# ECGv2_Board.net
KiCad netlist of a schematic drawn in EAGLE
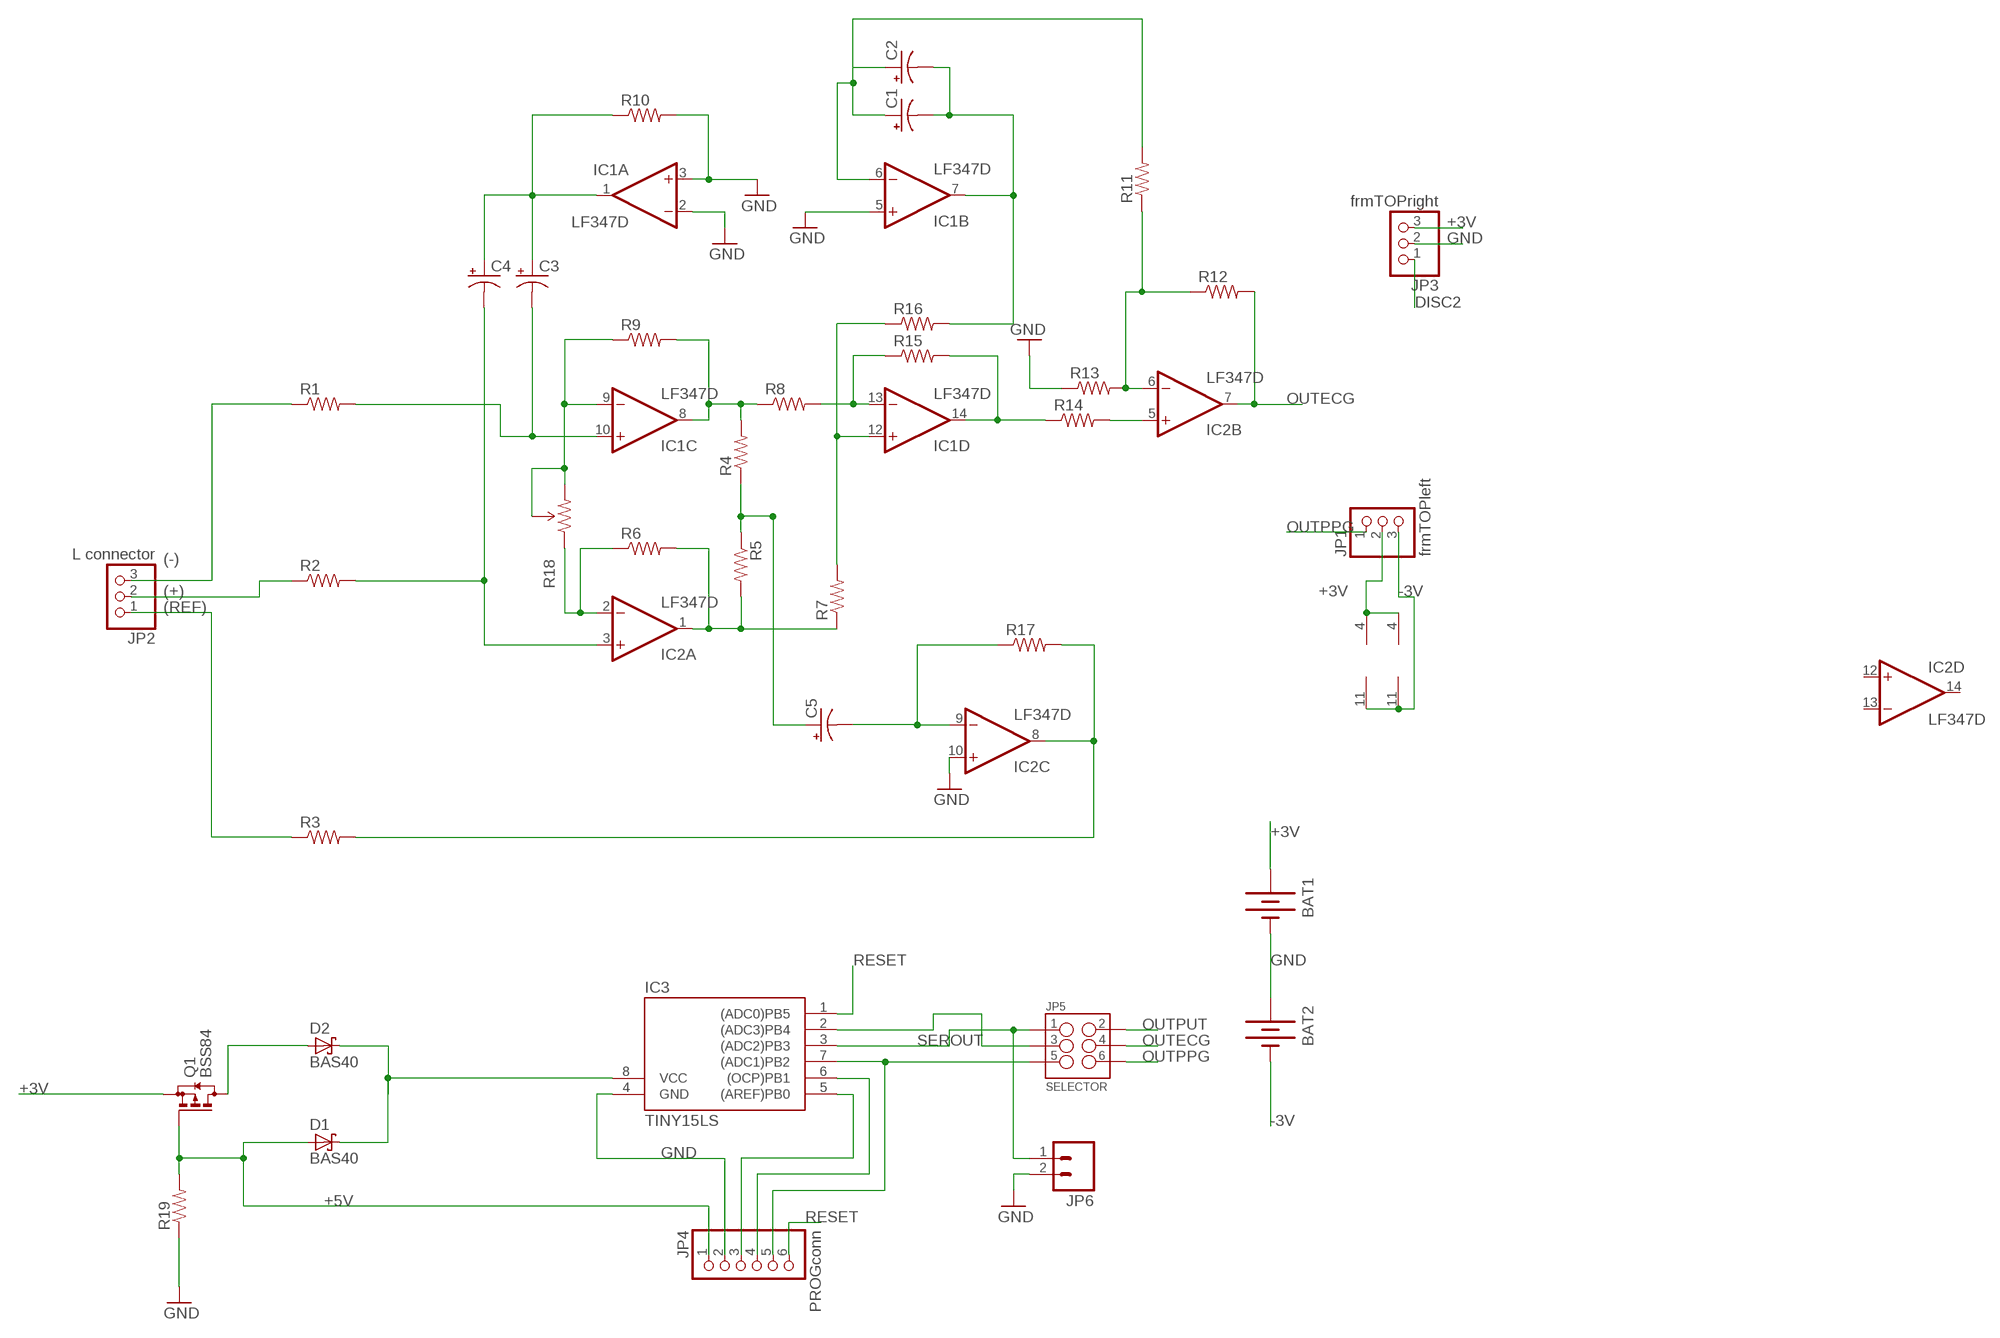
[diagram p0: schematic, sheet 1]

(export (version "E")
  (design (tool "Eeschema 10.0.6"))
  (components
    (comp (ref "BAT1")
      (value "BATTERY245MM")
      (footprint "eagle-import:BATTCON_245MM")
      (libsource (lib "eagle-import") (part "BATTERY245MM"))
    )
    (comp (ref "BAT2")
      (value "BATTERY245MM")
      (footprint "eagle-import:BATTCON_245MM")
      (libsource (lib "eagle-import") (part "BATTERY245MM"))
    )
    (comp (ref "C1")
      (value "CAP_POL1206-KIT")
      (footprint "eagle-import:EIA3216-KIT")
      (libsource (lib "eagle-import") (part "CAP_POL1206-KIT"))
    )
    (comp (ref "C2")
      (value "CAP_POL1206-KIT")
      (footprint "eagle-import:EIA3216-KIT")
      (libsource (lib "eagle-import") (part "CAP_POL1206-KIT"))
    )
    (comp (ref "C3")
      (value "CAP_POL1206-KIT")
      (footprint "eagle-import:EIA3216-KIT")
      (libsource (lib "eagle-import") (part "CAP_POL1206-KIT"))
    )
    (comp (ref "C4")
      (value "CAP_POL1206-KIT")
      (footprint "eagle-import:EIA3216-KIT")
      (libsource (lib "eagle-import") (part "CAP_POL1206-KIT"))
    )
    (comp (ref "C5")
      (value "CAP_POL1206-KIT")
      (footprint "eagle-import:EIA3216-KIT")
      (libsource (lib "eagle-import") (part "CAP_POL1206-KIT"))
    )
    (comp (ref "D1")
      (value "BAS40")
      (footprint "eagle-import:SOT23")
      (libsource (lib "eagle-import") (part "BAS40"))
    )
    (comp (ref "D2")
      (value "BAS40")
      (footprint "eagle-import:SOT23")
      (libsource (lib "eagle-import") (part "BAS40"))
    )
    (comp (ref "IC1")
      (value "LF347D")
      (footprint "eagle-import:SO14")
      (libsource (lib "eagle-import") (part "LF347D"))
    )
    (comp (ref "IC2")
      (value "LF347D")
      (footprint "eagle-import:SO14")
      (libsource (lib "eagle-import") (part "LF347D"))
    )
    (comp (ref "IC3")
      (value "TINY15LS")
      (footprint "eagle-import:SOIC8")
      (libsource (lib "eagle-import") (part "TINY15LS"))
    )
    (comp (ref "JP1")
      (value "frmTOPleft")
      (footprint "eagle-import:1X03")
      (libsource (lib "eagle-import") (part "PINHD-1X3"))
    )
    (comp (ref "JP2")
      (value "L connector")
      (footprint "eagle-import:1X03")
      (libsource (lib "eagle-import") (part "PINHD-1X3"))
    )
    (comp (ref "JP3")
      (value "frmTOPright")
      (footprint "eagle-import:1X03")
      (libsource (lib "eagle-import") (part "PINHD-1X3"))
    )
    (comp (ref "JP4")
      (value "PROGconn")
      (footprint "eagle-import:1X06-BIG")
      (libsource (lib "eagle-import") (part "PINHD-1X6B"))
    )
    (comp (ref "JP5")
      (value "SELECTOR")
      (footprint "eagle-import:2X3")
      (libsource (lib "eagle-import") (part "M03X2FEMALE"))
    )
    (comp (ref "JP6")
      (value "M02PTH")
      (footprint "eagle-import:1X02")
      (libsource (lib "eagle-import") (part "M02PTH"))
    )
    (comp (ref "Q1")
      (value "BSS84")
      (footprint "eagle-import:SOT23")
      (libsource (lib "eagle-import") (part "BSS84"))
    )
    (comp (ref "R1")
      (value "RESISTOR0402-RES")
      (footprint "eagle-import:0402-RES")
      (libsource (lib "eagle-import") (part "RESISTOR0402-RES"))
    )
    (comp (ref "R2")
      (value "RESISTOR0402-RES")
      (footprint "eagle-import:0402-RES")
      (libsource (lib "eagle-import") (part "RESISTOR0402-RES"))
    )
    (comp (ref "R3")
      (value "RESISTOR0402-RES")
      (footprint "eagle-import:0402-RES")
      (libsource (lib "eagle-import") (part "RESISTOR0402-RES"))
    )
    (comp (ref "R4")
      (value "RESISTOR0402-RES")
      (footprint "eagle-import:0402-RES")
      (libsource (lib "eagle-import") (part "RESISTOR0402-RES"))
    )
    (comp (ref "R5")
      (value "RESISTOR0402-RES")
      (footprint "eagle-import:0402-RES")
      (libsource (lib "eagle-import") (part "RESISTOR0402-RES"))
    )
    (comp (ref "R6")
      (value "RESISTOR0402-RES")
      (footprint "eagle-import:0402-RES")
      (libsource (lib "eagle-import") (part "RESISTOR0402-RES"))
    )
    (comp (ref "R7")
      (value "RESISTOR0402-RES")
      (footprint "eagle-import:0402-RES")
      (libsource (lib "eagle-import") (part "RESISTOR0402-RES"))
    )
    (comp (ref "R8")
      (value "RESISTOR0402-RES")
      (footprint "eagle-import:0402-RES")
      (libsource (lib "eagle-import") (part "RESISTOR0402-RES"))
    )
    (comp (ref "R9")
      (value "RESISTOR0402-RES")
      (footprint "eagle-import:0402-RES")
      (libsource (lib "eagle-import") (part "RESISTOR0402-RES"))
    )
    (comp (ref "R10")
      (value "RESISTOR0402-RES")
      (footprint "eagle-import:0402-RES")
      (libsource (lib "eagle-import") (part "RESISTOR0402-RES"))
    )
    (comp (ref "R11")
      (value "RESISTOR0402-RES")
      (footprint "eagle-import:0402-RES")
      (libsource (lib "eagle-import") (part "RESISTOR0402-RES"))
    )
    (comp (ref "R12")
      (value "RESISTOR0402-RES")
      (footprint "eagle-import:0402-RES")
      (libsource (lib "eagle-import") (part "RESISTOR0402-RES"))
    )
    (comp (ref "R13")
      (value "RESISTOR0402-RES")
      (footprint "eagle-import:0402-RES")
      (libsource (lib "eagle-import") (part "RESISTOR0402-RES"))
    )
    (comp (ref "R14")
      (value "RESISTOR0402-RES")
      (footprint "eagle-import:0402-RES")
      (libsource (lib "eagle-import") (part "RESISTOR0402-RES"))
    )
    (comp (ref "R15")
      (value "RESISTOR0402-RES")
      (footprint "eagle-import:0402-RES")
      (libsource (lib "eagle-import") (part "RESISTOR0402-RES"))
    )
    (comp (ref "R16")
      (value "RESISTOR0402-RES")
      (footprint "eagle-import:0402-RES")
      (libsource (lib "eagle-import") (part "RESISTOR0402-RES"))
    )
    (comp (ref "R17")
      (value "RESISTOR0402-RES")
      (footprint "eagle-import:0402-RES")
      (libsource (lib "eagle-import") (part "RESISTOR0402-RES"))
    )
    (comp (ref "R18")
      (value "TRIMPOT3362U-2")
      (footprint "eagle-import:3362U-2")
      (libsource (lib "eagle-import") (part "TRIMPOT3362U-2"))
    )
    (comp (ref "R19")
      (value "RESISTOR0402-RES")
      (footprint "eagle-import:0402-RES")
      (libsource (lib "eagle-import") (part "RESISTOR0402-RES"))
    )
  )
  (nets
    (net (code "1") (name "/(+)") (class "Default")
      (node (ref "JP2") (pin "2") (pinfunction "2_2") (pintype "passive"))
      (node (ref "R2") (pin "1") (pinfunction "1_1") (pintype "passive"))
    )
    (net (code "2") (name "/(-)") (class "Default")
      (node (ref "JP2") (pin "3") (pinfunction "3_3") (pintype "passive"))
      (node (ref "R1") (pin "1") (pinfunction "1_1") (pintype "passive"))
    )
    (net (code "3") (name "/(REF)") (class "Default")
      (node (ref "JP2") (pin "1") (pinfunction "1_1") (pintype "passive"))
      (node (ref "R3") (pin "1") (pinfunction "1_1") (pintype "passive"))
    )
    (net (code "4") (name "/+3V") (class "Default")
      (node (ref "BAT1") (pin "1") (pinfunction "+_1") (pintype "power_in"))
      (node (ref "BAT1") (pin "3") (pinfunction "+_3") (pintype "power_in"))
      (node (ref "IC1") (pin "4") (pinfunction "V+_4") (pintype "power_in"))
      (node (ref "IC2") (pin "4") (pinfunction "V+_4") (pintype "power_in"))
      (node (ref "JP1") (pin "2") (pinfunction "2_2") (pintype "passive"))
      (node (ref "JP3") (pin "3") (pinfunction "3_3") (pintype "passive"))
      (node (ref "Q1") (pin "2") (pinfunction "S_2") (pintype "passive"))
    )
    (net (code "5") (name "/+5V") (class "Default")
      (node (ref "D1") (pin "1") (pinfunction "A_1") (pintype "passive"))
      (node (ref "JP4") (pin "1") (pinfunction "1_1") (pintype "passive"))
      (node (ref "Q1") (pin "1") (pinfunction "G_1") (pintype "passive"))
      (node (ref "R19") (pin "2") (pinfunction "2_2") (pintype "passive"))
    )
    (net (code "6") (name "/-3V") (class "Default")
      (node (ref "BAT2") (pin "2") (pinfunction "-_2") (pintype "power_in"))
      (node (ref "IC1") (pin "11") (pinfunction "V-_11") (pintype "power_in"))
      (node (ref "IC2") (pin "11") (pinfunction "V-_11") (pintype "power_in"))
      (node (ref "JP1") (pin "3") (pinfunction "3_3") (pintype "passive"))
    )
    (net (code "7") (name "/DISC2") (class "Default")
      (node (ref "JP3") (pin "1") (pinfunction "1_1") (pintype "passive"))
    )
    (net (code "8") (name "/OUTECG") (class "Default")
      (node (ref "IC2") (pin "7") (pinfunction "OUT_7") (pintype "output"))
      (node (ref "JP5") (pin "4") (pinfunction "4_4") (pintype "bidirectional"))
      (node (ref "R12") (pin "2") (pinfunction "2_2") (pintype "passive"))
    )
    (net (code "9") (name "/OUTPPG") (class "Default")
      (node (ref "JP1") (pin "1") (pinfunction "1_1") (pintype "passive"))
      (node (ref "JP5") (pin "6") (pinfunction "6_6") (pintype "bidirectional"))
    )
    (net (code "10") (name "/OUTPUT") (class "Default")
      (node (ref "JP5") (pin "2") (pinfunction "2_2") (pintype "bidirectional"))
    )
    (net (code "11") (name "/RESET") (class "Default")
      (node (ref "IC3") (pin "1") (pinfunction "(ADC0)PB5_1") (pintype "bidirectional"))
      (node (ref "JP4") (pin "6") (pinfunction "6_6") (pintype "passive"))
    )
    (net (code "12") (name "/SEROUT") (class "Default")
      (node (ref "IC3") (pin "3") (pinfunction "(ADC2)PB3_3") (pintype "bidirectional"))
      (node (ref "JP5") (pin "1") (pinfunction "1_1") (pintype "bidirectional"))
      (node (ref "JP6") (pin "1") (pinfunction "1_1") (pintype "passive"))
    )
    (net (code "13") (name "GND") (class "Default")
      (node (ref "BAT1") (pin "2") (pinfunction "-_2") (pintype "power_in"))
      (node (ref "BAT2") (pin "1") (pinfunction "+_1") (pintype "power_in"))
      (node (ref "BAT2") (pin "3") (pinfunction "+_3") (pintype "power_in"))
      (node (ref "IC1") (pin "2") (pinfunction "-IN_2") (pintype "input"))
      (node (ref "IC1") (pin "3") (pinfunction "+IN_3") (pintype "input"))
      (node (ref "IC1") (pin "5") (pinfunction "+IN_5") (pintype "input"))
      (node (ref "IC2") (pin "10") (pinfunction "+IN_10") (pintype "input"))
      (node (ref "IC3") (pin "4") (pinfunction "GND_4") (pintype "power_in"))
      (node (ref "JP3") (pin "2") (pinfunction "2_2") (pintype "passive"))
      (node (ref "JP4") (pin "2") (pinfunction "2_2") (pintype "passive"))
      (node (ref "JP6") (pin "2") (pinfunction "2_2") (pintype "passive"))
      (node (ref "R10") (pin "2") (pinfunction "2_2") (pintype "passive"))
      (node (ref "R13") (pin "1") (pinfunction "1_1") (pintype "passive"))
      (node (ref "R19") (pin "1") (pinfunction "1_1") (pintype "passive"))
    )
    (net (code "14") (name "Net-(C1-+)") (class "Default")
      (node (ref "C1") (pin "A") (pinfunction "+_A") (pintype "passive"))
      (node (ref "C2") (pin "A") (pinfunction "+_A") (pintype "passive"))
      (node (ref "IC1") (pin "6") (pinfunction "-IN_6") (pintype "input"))
      (node (ref "R11") (pin "2") (pinfunction "2_2") (pintype "passive"))
    )
    (net (code "15") (name "Net-(C1--)") (class "Default")
      (node (ref "C1") (pin "C") (pinfunction "-_C") (pintype "passive"))
      (node (ref "C2") (pin "C") (pinfunction "-_C") (pintype "passive"))
      (node (ref "IC1") (pin "7") (pinfunction "OUT_7") (pintype "output"))
      (node (ref "R16") (pin "2") (pinfunction "2_2") (pintype "passive"))
    )
    (net (code "16") (name "Net-(C3-+)") (class "Default")
      (node (ref "C3") (pin "A") (pinfunction "+_A") (pintype "passive"))
      (node (ref "C4") (pin "A") (pinfunction "+_A") (pintype "passive"))
      (node (ref "IC1") (pin "1") (pinfunction "OUT_1") (pintype "output"))
      (node (ref "R10") (pin "1") (pinfunction "1_1") (pintype "passive"))
    )
    (net (code "17") (name "Net-(C3--)") (class "Default")
      (node (ref "C3") (pin "C") (pinfunction "-_C") (pintype "passive"))
      (node (ref "IC1") (pin "10") (pinfunction "+IN_10") (pintype "input"))
      (node (ref "R1") (pin "2") (pinfunction "2_2") (pintype "passive"))
    )
    (net (code "18") (name "Net-(C4--)") (class "Default")
      (node (ref "C4") (pin "C") (pinfunction "-_C") (pintype "passive"))
      (node (ref "IC2") (pin "3") (pinfunction "+IN_3") (pintype "input"))
      (node (ref "R2") (pin "2") (pinfunction "2_2") (pintype "passive"))
    )
    (net (code "19") (name "Net-(C5-+)") (class "Default")
      (node (ref "C5") (pin "A") (pinfunction "+_A") (pintype "passive"))
      (node (ref "R4") (pin "1") (pinfunction "1_1") (pintype "passive"))
      (node (ref "R5") (pin "1") (pinfunction "1_1") (pintype "passive"))
    )
    (net (code "20") (name "Net-(C5--)") (class "Default")
      (node (ref "C5") (pin "C") (pinfunction "-_C") (pintype "passive"))
      (node (ref "IC2") (pin "9") (pinfunction "-IN_9") (pintype "input"))
      (node (ref "R17") (pin "1") (pinfunction "1_1") (pintype "passive"))
    )
    (net (code "21") (name "Net-(D1-C)") (class "Default")
      (node (ref "D1") (pin "3") (pinfunction "C_3") (pintype "passive"))
      (node (ref "D2") (pin "3") (pinfunction "C_3") (pintype "passive"))
      (node (ref "IC3") (pin "8") (pinfunction "VCC_8") (pintype "power_in"))
    )
    (net (code "22") (name "Net-(D2-A)") (class "Default")
      (node (ref "D2") (pin "1") (pinfunction "A_1") (pintype "passive"))
      (node (ref "Q1") (pin "3") (pinfunction "D_3") (pintype "passive"))
    )
    (net (code "23") (name "Net-(IC1C--IN)") (class "Default")
      (node (ref "IC1") (pin "9") (pinfunction "-IN_9") (pintype "input"))
      (node (ref "R18") (pin "2") (pinfunction "WIPER_2") (pintype "passive"))
      (node (ref "R18") (pin "3") (pinfunction "CW_3") (pintype "passive"))
      (node (ref "R9") (pin "1") (pinfunction "1_1") (pintype "passive"))
    )
    (net (code "24") (name "Net-(IC1C-OUT)") (class "Default")
      (node (ref "IC1") (pin "8") (pinfunction "OUT_8") (pintype "output"))
      (node (ref "R4") (pin "2") (pinfunction "2_2") (pintype "passive"))
      (node (ref "R8") (pin "1") (pinfunction "1_1") (pintype "passive"))
      (node (ref "R9") (pin "2") (pinfunction "2_2") (pintype "passive"))
    )
    (net (code "25") (name "Net-(IC1D-+IN)") (class "Default")
      (node (ref "IC1") (pin "12") (pinfunction "+IN_12") (pintype "input"))
      (node (ref "R16") (pin "1") (pinfunction "1_1") (pintype "passive"))
      (node (ref "R7") (pin "2") (pinfunction "2_2") (pintype "passive"))
    )
    (net (code "26") (name "Net-(IC1D--IN)") (class "Default")
      (node (ref "IC1") (pin "13") (pinfunction "-IN_13") (pintype "input"))
      (node (ref "R15") (pin "1") (pinfunction "1_1") (pintype "passive"))
      (node (ref "R8") (pin "2") (pinfunction "2_2") (pintype "passive"))
    )
    (net (code "27") (name "Net-(IC1D-OUT)") (class "Default")
      (node (ref "IC1") (pin "14") (pinfunction "OUT_14") (pintype "output"))
      (node (ref "R14") (pin "1") (pinfunction "1_1") (pintype "passive"))
      (node (ref "R15") (pin "2") (pinfunction "2_2") (pintype "passive"))
    )
    (net (code "28") (name "Net-(IC2A--IN)") (class "Default")
      (node (ref "IC2") (pin "2") (pinfunction "-IN_2") (pintype "input"))
      (node (ref "R18") (pin "1") (pinfunction "CCW_1") (pintype "passive"))
      (node (ref "R6") (pin "1") (pinfunction "1_1") (pintype "passive"))
    )
    (net (code "29") (name "Net-(IC2A-OUT)") (class "Default")
      (node (ref "IC2") (pin "1") (pinfunction "OUT_1") (pintype "output"))
      (node (ref "R5") (pin "2") (pinfunction "2_2") (pintype "passive"))
      (node (ref "R6") (pin "2") (pinfunction "2_2") (pintype "passive"))
      (node (ref "R7") (pin "1") (pinfunction "1_1") (pintype "passive"))
    )
    (net (code "30") (name "Net-(IC2B-+IN)") (class "Default")
      (node (ref "IC2") (pin "5") (pinfunction "+IN_5") (pintype "input"))
      (node (ref "R14") (pin "2") (pinfunction "2_2") (pintype "passive"))
    )
    (net (code "31") (name "Net-(IC2B--IN)") (class "Default")
      (node (ref "IC2") (pin "6") (pinfunction "-IN_6") (pintype "input"))
      (node (ref "R11") (pin "1") (pinfunction "1_1") (pintype "passive"))
      (node (ref "R12") (pin "1") (pinfunction "1_1") (pintype "passive"))
      (node (ref "R13") (pin "2") (pinfunction "2_2") (pintype "passive"))
    )
    (net (code "32") (name "Net-(IC2C-OUT)") (class "Default")
      (node (ref "IC2") (pin "8") (pinfunction "OUT_8") (pintype "output"))
      (node (ref "R17") (pin "2") (pinfunction "2_2") (pintype "passive"))
      (node (ref "R3") (pin "2") (pinfunction "2_2") (pintype "passive"))
    )
    (net (code "33") (name "Net-(IC3-(ADC1)PB2)") (class "Default")
      (node (ref "IC3") (pin "7") (pinfunction "(ADC1)PB2_7") (pintype "bidirectional"))
      (node (ref "JP4") (pin "5") (pinfunction "5_5") (pintype "passive"))
      (node (ref "JP5") (pin "5") (pinfunction "5_5") (pintype "bidirectional"))
    )
    (net (code "34") (name "Net-(IC3-(ADC3)PB4)") (class "Default")
      (node (ref "IC3") (pin "2") (pinfunction "(ADC3)PB4_2") (pintype "bidirectional"))
      (node (ref "JP5") (pin "3") (pinfunction "3_3") (pintype "bidirectional"))
    )
    (net (code "35") (name "Net-(IC3-(AREF)PB0)") (class "Default")
      (node (ref "IC3") (pin "5") (pinfunction "(AREF)PB0_5") (pintype "bidirectional"))
      (node (ref "JP4") (pin "3") (pinfunction "3_3") (pintype "passive"))
    )
    (net (code "36") (name "Net-(IC3-(OCP)PB1)") (class "Default")
      (node (ref "IC3") (pin "6") (pinfunction "(OCP)PB1_6") (pintype "bidirectional"))
      (node (ref "JP4") (pin "4") (pinfunction "4_4") (pintype "passive"))
    )
    (net (code "37") (name "unconnected-(IC2D-+IN-Pad12)") (class "Default")
      (node (ref "IC2") (pin "12") (pinfunction "+IN_12") (pintype "input"))
    )
    (net (code "38") (name "unconnected-(IC2D--IN-Pad13)") (class "Default")
      (node (ref "IC2") (pin "13") (pinfunction "-IN_13") (pintype "input"))
    )
    (net (code "39") (name "unconnected-(IC2D-OUT-Pad14)") (class "Default")
      (node (ref "IC2") (pin "14") (pinfunction "OUT_14") (pintype "output"))
    )
  )
)
